# NegativePwr.net
KiCad netlist of a schematic drawn in Altium Designer
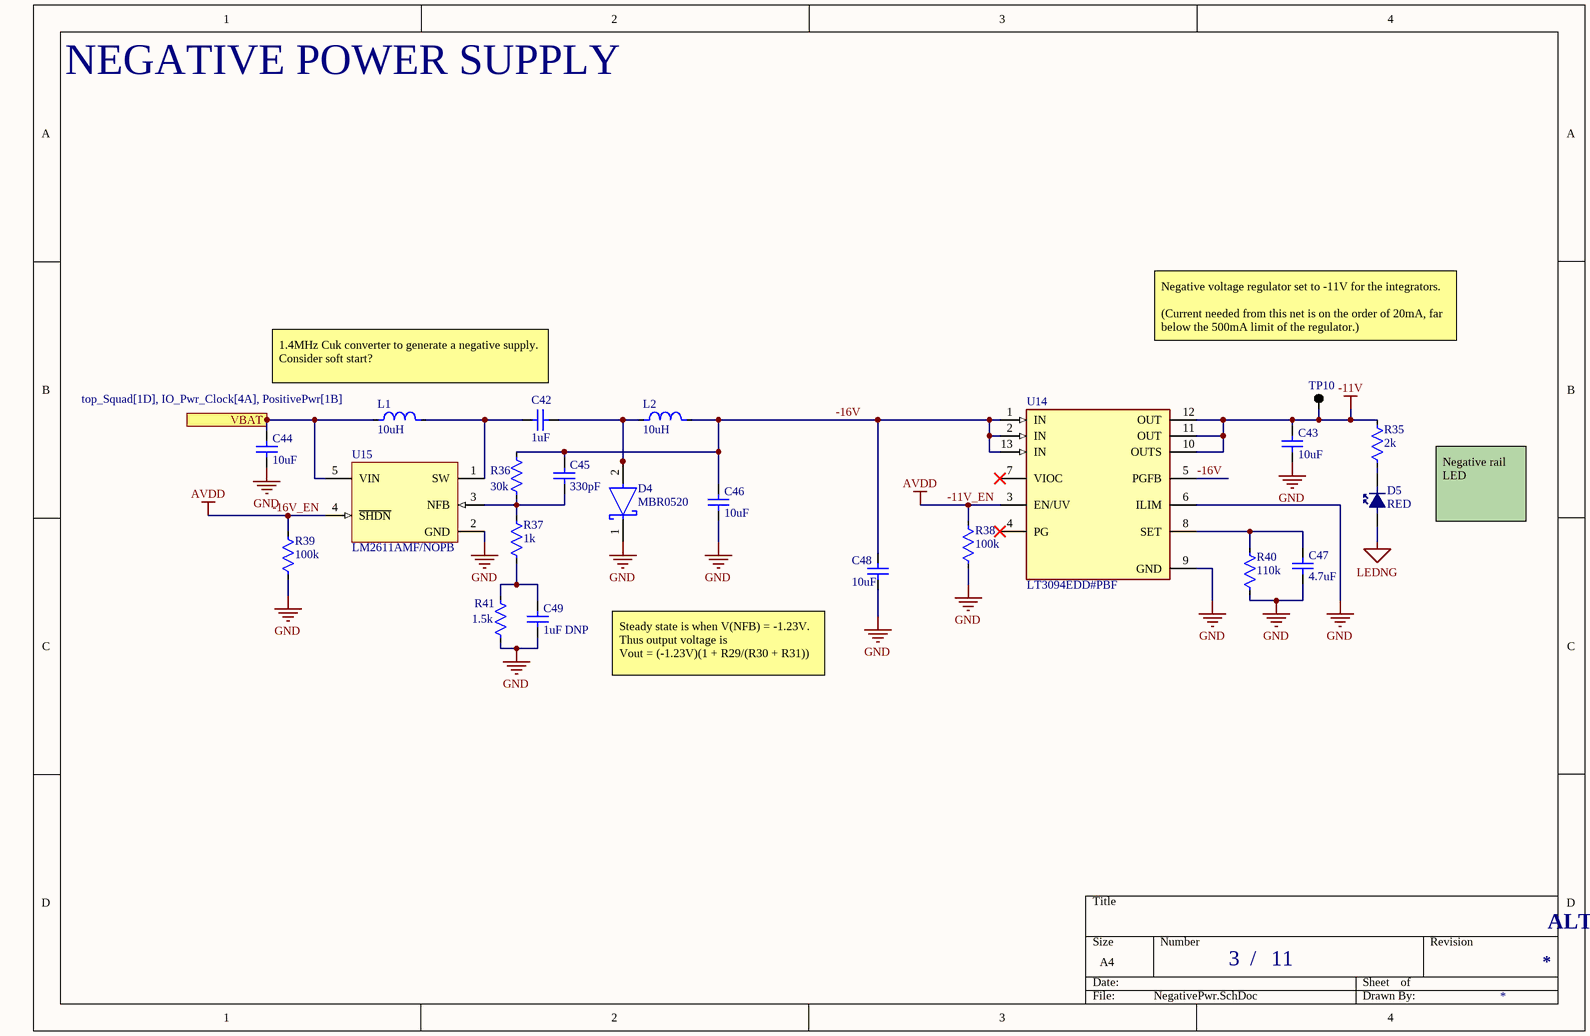
[diagram p0: NegativePwr.SchDoc]

(export (version "E")
  (design (tool "Eeschema 10.0.6"))
  (components
    (comp (ref "C42")
      (value "1uF")
      (footprint "CAP 0603 IPC MID DENSITY")
      (description "Murata GRT188R61H105KE13D - Cap MLCC AEC-Q200 X5R 1uF 50V 0603")
      (fields (field (name "MF") "Murata") (field (name "MP") "GRT188R61H105KE13D"))
      (libsource (lib "ALTAIR_PD_Capacitors") (part "CAP"))
    )
    (comp (ref "C43")
      (value "10uF")
      (footprint "CAP 0805 IPC MID DENSITY")
      (description "Murata GRM21BR61E106KA73L - Cap Ceramic 10uF 10% 25V X5R 0805")
      (fields (field (name "MF") "Murata") (field (name "MP") "GRM21BR61E106KA73L"))
      (libsource (lib "ALTAIR_PD_Capacitors") (part "CAP"))
    )
    (comp (ref "C44")
      (value "10uF")
      (footprint "CAP 0805 IPC MID DENSITY")
      (description "Murata GRM21BR61E106KA73L - Cap Ceramic 10uF 10% 25V X5R 0805")
      (fields (field (name "MF") "Murata") (field (name "MP") "GRM21BR61E106KA73L"))
      (libsource (lib "ALTAIR_PD_Capacitors") (part "CAP"))
    )
    (comp (ref "C45")
      (value "330pF")
      (footprint "CAP 1206 NON-IPC KEMET NP0")
      (description "Kemet C1206C331J5GACTU - Cap Ceramic 330pF 50V 5% NP0 1206")
      (fields (field (name "MF") "Kemet") (field (name "MP") "C1206C331J5GACTU"))
      (libsource (lib "ALTAIR_PD_Capacitors") (part "CAP"))
    )
    (comp (ref "C46")
      (value "10uF")
      (footprint "CAP 0805 IPC MID DENSITY")
      (description "Murata GRM21BR61E106KA73L - Cap Ceramic 10uF 10% 25V X5R 0805")
      (fields (field (name "MF") "Murata") (field (name "MP") "GRM21BR61E106KA73L"))
      (libsource (lib "ALTAIR_PD_Capacitors") (part "CAP"))
    )
    (comp (ref "C47")
      (value "4.7uF")
      (footprint "CAP 0805 NON-IPC KEMET X5R")
      (description "Kemet C0805C475K8PACTU - Cap Ceramic 4.7uF 10V X5R 0805")
      (fields (field (name "MF") "Kemet") (field (name "MP") "C0805C475K8PACTU"))
      (libsource (lib "ALTAIR_PD_Capacitors") (part "CAP"))
    )
    (comp (ref "C48")
      (value "10uF")
      (footprint "CAP 0805 IPC MID DENSITY")
      (description "Murata GRM21BR61E106KA73L - Cap Ceramic 10uF 10% 25V X5R 0805")
      (fields (field (name "MF") "Murata") (field (name "MP") "GRM21BR61E106KA73L"))
      (libsource (lib "ALTAIR_PD_Capacitors") (part "CAP"))
    )
    (comp (ref "C49")
      (value "1uF DNP")
      (footprint "CAP 0603 IPC MID DENSITY")
      (description "Murata GRT188R61H105KE13D - Cap MLCC AEC-Q200 X5R 1uF 50V 0603")
      (fields (field (name "MF") "Murata") (field (name "MP") "GRT188R61H105KE13D"))
      (libsource (lib "ALTAIR_PD_Capacitors") (part "CAP"))
    )
    (comp (ref "D4")
      (value "MBR0520")
      (footprint "SOD-123 ONSEMI SMALL PADS")
      (description "DIODE SCHOTTKY 20V 500MA SOD123")
      (fields (field (name "MF") "onsemi") (field (name "MP") "MBR0520LT1G"))
      (libsource (lib "ALTAIR_PD_Diodes") (part "Schottky"))
    )
    (comp (ref "D5")
      (value "RED")
      (footprint "LED 0603 MID DENSITY")
      (description "LED RED CLEAR 0603 SMD")
      (fields (field (name "MF") "Wurth Electronics") (field (name "MP") "150060RS75000"))
      (libsource (lib "ALTAIR_PD_Diodes") (part "LED-blue"))
    )
    (comp (ref "L1")
      (value "10uH")
      (footprint "IND VLS3012CX-1 NONSTANDARD TDK")
      (description "TDK VLS3012CX-100M-1 - Inductor 10uH 20% 1.25A 0.324Ohm NonstandardPkg")
      (fields (field (name "TOLERANCE") "20%") (field (name "MF") "TDK Corporation"))
      (libsource (lib "ALTAIR_PD_Inductors") (part "IND"))
    )
    (comp (ref "L2")
      (value "10uH")
      (footprint "IND VLS3012CX-1 NONSTANDARD TDK")
      (description "TDK VLS3012CX-100M-1 - Inductor 10uH 20% 1.25A 0.324Ohm NonstandardPkg")
      (fields (field (name "TOLERANCE") "20%") (field (name "MF") "TDK Corporation"))
      (libsource (lib "ALTAIR_PD_Inductors") (part "IND"))
    )
    (comp (ref "R35")
      (value "2k")
      (footprint "RES 0603 IPC MID DENSITY")
      (description "Panasonic ERJ-3EKF2001V Res Thick Film 0603 2K Ohm 1% 1/10W ±100ppm/°C")
      (fields (field (name "MF") "Panasonic Electronic Components") (field (name "MP") "ERJ-3EKF2001V"))
      (libsource (lib "ALTAIR_PD_Resistors") (part "RES"))
    )
    (comp (ref "R36")
      (value "30k")
      (footprint "RES 0805 IPC HIGH DENSITY")
      (description "Panasonic ERA-6AEB303V - Res 30kOhm 0.1% 1/8W 0805")
      (fields (field (name "MF") "Panasonic Electronic Components") (field (name "MP") "ERA-6AEB303V"))
      (libsource (lib "ALTAIR_PD_Resistors") (part "RES"))
    )
    (comp (ref "R37")
      (value "1k")
      (footprint "RES 0603 IPC MID DENSITY")
      (description "Panasonic ERJ-U03F1001V - Res SMD 1 kOhm 1% 1/10W 0603")
      (fields (field (name "MF") "Panasonic Electronic Components") (field (name "MP") "ERJ-U03F1001V"))
      (libsource (lib "ALTAIR_PD_Resistors") (part "RES"))
    )
    (comp (ref "R38")
      (value "100k")
      (footprint "RES 0603 IPC MID DENSITY")
      (description "Panasonic ERA-3ARB104V - Res SMD 0603 0.1% 0.10W T.C. 10ppm 100K")
      (fields (field (name "MF") "Panasonic Electronic Components") (field (name "MP") "ERA-3ARB104V"))
      (libsource (lib "ALTAIR_PD_Resistors") (part "RES"))
    )
    (comp (ref "R39")
      (value "100k")
      (footprint "RES 0603 IPC MID DENSITY")
      (description "Panasonic ERA-3ARB104V - Res SMD 0603 0.1% 0.10W T.C. 10ppm 100K")
      (fields (field (name "MF") "Panasonic Electronic Components") (field (name "MP") "ERA-3ARB104V"))
      (libsource (lib "ALTAIR_PD_Resistors") (part "RES"))
    )
    (comp (ref "R40")
      (value "110k")
      (footprint "RES 0603 IPC MID DENSITY")
      (description "Panasonic ERA-3AEB114V - Res 110k 0.1% 1/10W SMD 0603")
      (fields (field (name "MF") "Panasonic Electronic Components") (field (name "MP") "ERA-3AEB114V"))
      (libsource (lib "ALTAIR_PD_Resistors") (part "RES"))
    )
    (comp (ref "R41")
      (value "1.5k")
      (footprint "RES 1206 NON-IPC VISHAY")
      (description "Vishay TNPU12061K50BZEN00 - Res 1.5kOhm 0.1% 1/4W 1206")
      (fields (field (name "MF") "Vishay Dale") (field (name "MP") "TNPU12061K50BZEN00"))
      (libsource (lib "ALTAIR_PD_Resistors") (part "RES"))
    )
    (comp (ref "TP10")
      (value "Testpoint")
      (footprint "TESTPOINT THT")
      (libsource (lib "ALTAIR_PD_Testpoint") (part "Testpoint"))
    )
    (comp (ref "U14")
      (value "LT3094EDD#PBF")
      (footprint "12DFN 3x3MM EP IPC MID DENSITY")
      (description "-20V 500mA Ultralow Noise Ultrahigh PSRR Adjustable Negative Linear Regulator 12DFN")
      (fields (field (name "MF") "Analog Devices"))
      (libsource (lib "ALTAIR_PD_Regulators") (part "LT3094EDD#PBF"))
    )
    (comp (ref "U15")
      (value "LM2611AMF/NOPB")
      (footprint "SOT23-5 MID DENSITY")
      (description "1.4MHz Cuk Converter, 5-pin SOT-23, Pb-Free")
      (fields (field (name "MF") "Texas Instruments"))
      (libsource (lib "ALTAIR_PD_Converters") (part "LM2611AMF"))
    )
  )
  (nets
    (net (code "1") (name "-11V") (class "Default")
      (node (ref "C43") (pin "1") (pinfunction "1_1") (pintype "passive"))
      (node (ref "R35") (pin "2") (pinfunction "2_2") (pintype "passive"))
      (node (ref "TP10") (pin "1") (pinfunction "1_1") (pintype "passive"))
      (node (ref "U14") (pin "10") (pinfunction "OUTS_10") (pintype "power_in"))
      (node (ref "U14") (pin "11") (pinfunction "OUT_11") (pintype "power_in"))
      (node (ref "U14") (pin "12") (pinfunction "OUT_12") (pintype "power_in"))
    )
    (net (code "2") (name "/-16V") (class "Default")
      (node (ref "C45") (pin "1") (pinfunction "1_1") (pintype "passive"))
      (node (ref "C46") (pin "1") (pinfunction "1_1") (pintype "passive"))
      (node (ref "C48") (pin "1") (pinfunction "1_1") (pintype "passive"))
      (node (ref "L2") (pin "2") (pinfunction "2_2") (pintype "passive"))
      (node (ref "R36") (pin "2") (pinfunction "2_2") (pintype "passive"))
      (node (ref "U14") (pin "1") (pinfunction "IN_1") (pintype "input"))
      (node (ref "U14") (pin "13") (pinfunction "IN_13") (pintype "input"))
      (node (ref "U14") (pin "2") (pinfunction "IN_2") (pintype "input"))
      (node (ref "U14") (pin "5") (pinfunction "PGFB_5") (pintype "passive"))
    )
    (net (code "3") (name "/VBAT") (class "Default")
      (node (ref "C44") (pin "2") (pinfunction "2_2") (pintype "passive"))
      (node (ref "L1") (pin "1") (pinfunction "1_1") (pintype "passive"))
      (node (ref "U15") (pin "5") (pinfunction "VIN_5") (pintype "power_in"))
    )
    (net (code "4") (name "AVDD") (class "Default")
      (node (ref "R38") (pin "1") (pinfunction "1_1") (pintype "passive"))
      (node (ref "R39") (pin "1") (pinfunction "1_1") (pintype "passive"))
      (node (ref "U14") (pin "3") (pinfunction "EN/UV_3") (pintype "passive"))
      (node (ref "U15") (pin "4") (pinfunction "~{SHDN}_4") (pintype "input"))
    )
    (net (code "5") (name "GND") (class "Default")
      (node (ref "C43") (pin "2") (pinfunction "2_2") (pintype "passive"))
      (node (ref "C44") (pin "1") (pinfunction "1_1") (pintype "passive"))
      (node (ref "C46") (pin "2") (pinfunction "2_2") (pintype "passive"))
      (node (ref "C47") (pin "2") (pinfunction "2_2") (pintype "passive"))
      (node (ref "C48") (pin "2") (pinfunction "2_2") (pintype "passive"))
      (node (ref "C49") (pin "2") (pinfunction "2_2") (pintype "passive"))
      (node (ref "D4") (pin "1") (pinfunction "C_1") (pintype "passive"))
      (node (ref "R38") (pin "2") (pinfunction "2_2") (pintype "passive"))
      (node (ref "R39") (pin "2") (pinfunction "2_2") (pintype "passive"))
      (node (ref "R40") (pin "2") (pinfunction "2_2") (pintype "passive"))
      (node (ref "R41") (pin "1") (pinfunction "1_1") (pintype "passive"))
      (node (ref "U14") (pin "6") (pinfunction "ILIM_6") (pintype "passive"))
      (node (ref "U14") (pin "9") (pinfunction "GND_9") (pintype "power_in"))
      (node (ref "U15") (pin "2") (pinfunction "GND_2") (pintype "power_in"))
    )
    (net (code "6") (name "LEDNG") (class "Default")
      (node (ref "D5") (pin "2") (pinfunction "2_2") (pintype "passive"))
    )
    (net (code "7") (name "Net-(C49-Pad1)") (class "Default")
      (node (ref "C49") (pin "1") (pinfunction "1_1") (pintype "passive"))
      (node (ref "R37") (pin "1") (pinfunction "1_1") (pintype "passive"))
      (node (ref "R41") (pin "2") (pinfunction "2_2") (pintype "passive"))
    )
    (net (code "8") (name "Net-(D4-A)") (class "Default")
      (node (ref "C42") (pin "2") (pinfunction "2_2") (pintype "passive"))
      (node (ref "D4") (pin "2") (pinfunction "A_2") (pintype "passive"))
      (node (ref "L2") (pin "1") (pinfunction "1_1") (pintype "passive"))
    )
    (net (code "9") (name "Net-(D5-Pad1)") (class "Default")
      (node (ref "D5") (pin "1") (pinfunction "1_1") (pintype "passive"))
      (node (ref "R35") (pin "1") (pinfunction "1_1") (pintype "passive"))
    )
    (net (code "10") (name "Net-(U14-SET)") (class "Default")
      (node (ref "C47") (pin "1") (pinfunction "1_1") (pintype "passive"))
      (node (ref "R40") (pin "1") (pinfunction "1_1") (pintype "passive"))
      (node (ref "U14") (pin "8") (pinfunction "SET_8") (pintype "passive"))
    )
    (net (code "11") (name "Net-(U15-NFB)") (class "Default")
      (node (ref "C45") (pin "2") (pinfunction "2_2") (pintype "passive"))
      (node (ref "R36") (pin "1") (pinfunction "1_1") (pintype "passive"))
      (node (ref "R37") (pin "2") (pinfunction "2_2") (pintype "passive"))
      (node (ref "U15") (pin "3") (pinfunction "NFB_3") (pintype "input"))
    )
    (net (code "12") (name "Net-(U15-SW)") (class "Default")
      (node (ref "C42") (pin "1") (pinfunction "1_1") (pintype "passive"))
      (node (ref "L1") (pin "2") (pinfunction "2_2") (pintype "passive"))
      (node (ref "U15") (pin "1") (pinfunction "SW_1") (pintype "power_in"))
    )
    (net (code "13") (name "unconnected-(U14-PG-Pad4)") (class "Default")
      (node (ref "U14") (pin "4") (pinfunction "PG_4") (pintype "passive+no_connect"))
    )
    (net (code "14") (name "unconnected-(U14-VIOC-Pad7)") (class "Default")
      (node (ref "U14") (pin "7") (pinfunction "VIOC_7") (pintype "passive+no_connect"))
    )
  )
)
